# W104X.net
KiCad netlist of a schematic drawn in EAGLE
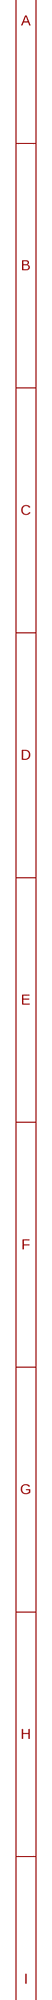
[diagram p0: schematic, sheet 1, part 1 of 2]
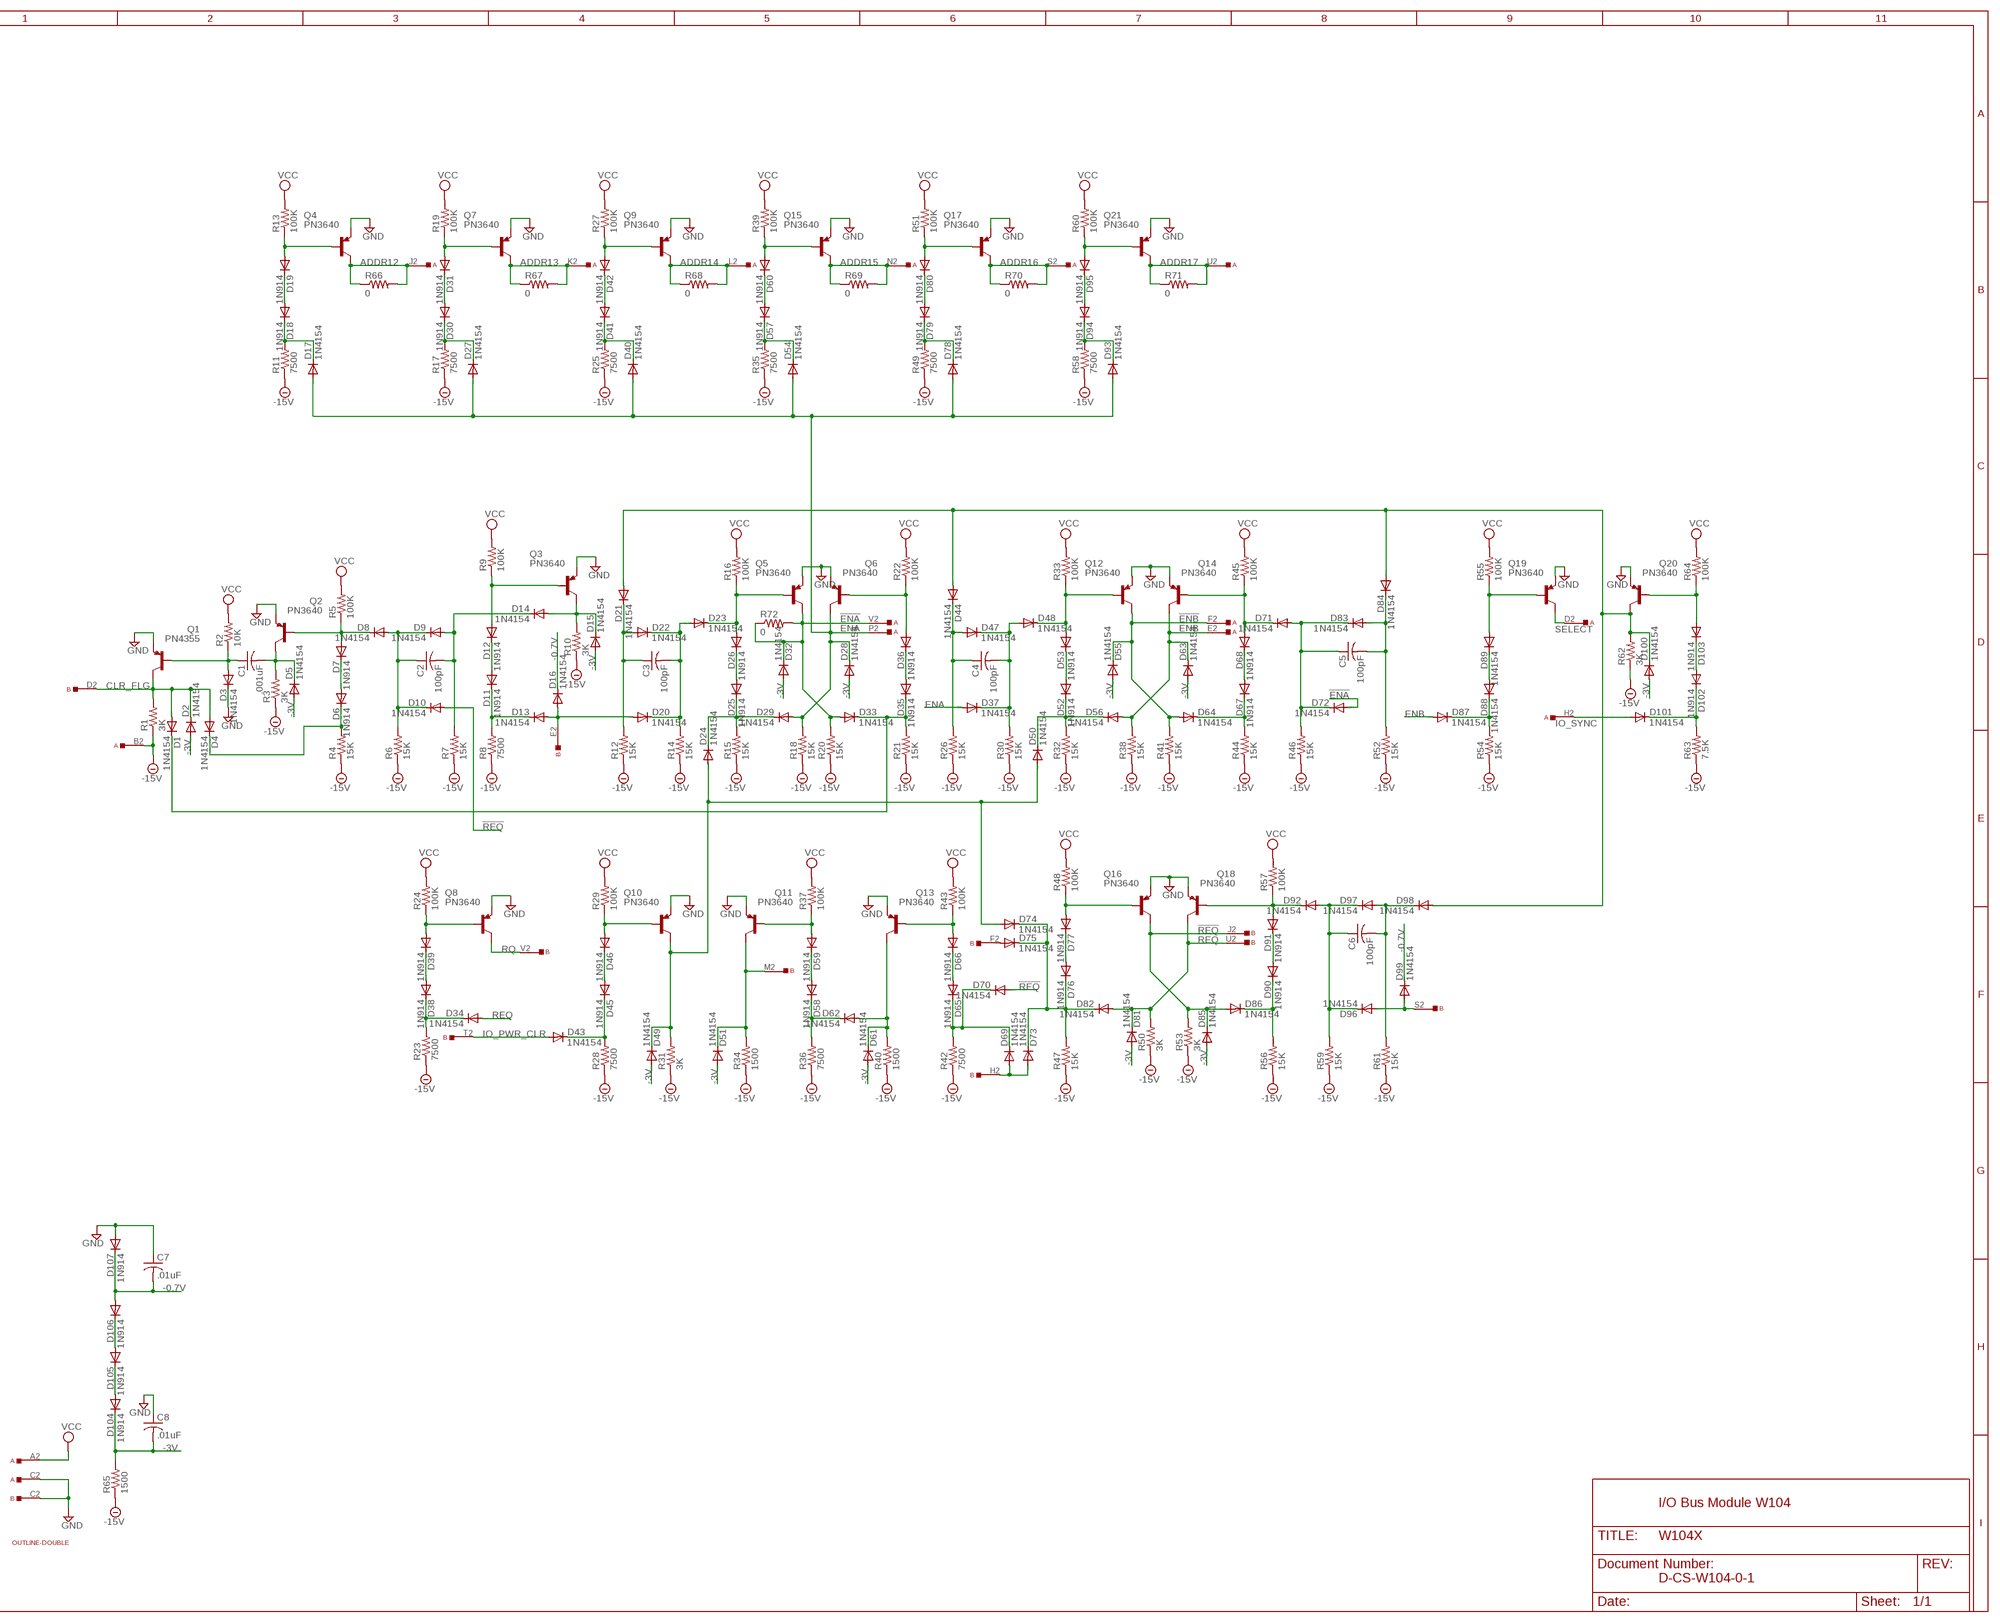
[diagram p1: schematic, sheet 1, part 2 of 2]

(export (version "E")
  (design (tool "Eeschema 10.0.6"))
  (components
    (comp (ref "A")
      (value "SS-TOP")
      (footprint "eagle-import:EDGE-CON1")
      (libsource (lib "eagle-import") (part "SS-TOP"))
    )
    (comp (ref "B")
      (value "SS-TOP")
      (footprint "eagle-import:EDGE-CON1")
      (libsource (lib "eagle-import") (part "SS-TOP"))
    )
    (comp (ref "C1")
      (value ".001uF")
      (footprint "eagle-import:C063-025X075")
      (libsource (lib "eagle-import") (part "C-US"))
    )
    (comp (ref "C2")
      (value "100pF")
      (footprint "eagle-import:C150-054X183")
      (libsource (lib "eagle-import") (part "C-US150-054X183"))
    )
    (comp (ref "C3")
      (value "100pF")
      (footprint "eagle-import:C150-054X183")
      (libsource (lib "eagle-import") (part "C-US150-054X183"))
    )
    (comp (ref "C4")
      (value "100pF")
      (footprint "eagle-import:C150-054X183")
      (libsource (lib "eagle-import") (part "C-US150-054X183"))
    )
    (comp (ref "C5")
      (value "100pF")
      (footprint "eagle-import:C150-054X183")
      (libsource (lib "eagle-import") (part "C-US150-054X183"))
    )
    (comp (ref "C6")
      (value "100pF")
      (footprint "eagle-import:C150-054X183")
      (libsource (lib "eagle-import") (part "C-US150-054X183"))
    )
    (comp (ref "C7")
      (value ".01uF")
      (footprint "eagle-import:C063-025X075")
      (libsource (lib "eagle-import") (part "C-US"))
    )
    (comp (ref "C8")
      (value ".01uF")
      (footprint "eagle-import:C063-025X075")
      (libsource (lib "eagle-import") (part "C-US"))
    )
    (comp (ref "D1")
      (value "1N4154")
      (footprint "eagle-import:DO35-10")
      (libsource (lib "eagle-import") (part "DIODE-DO35-10"))
    )
    (comp (ref "D2")
      (value "1N4154")
      (footprint "eagle-import:DO35-10")
      (libsource (lib "eagle-import") (part "DIODE-DO35-10"))
    )
    (comp (ref "D3")
      (value "1N4154")
      (footprint "eagle-import:DO35-10")
      (libsource (lib "eagle-import") (part "DIODE-DO35-10"))
    )
    (comp (ref "D4")
      (value "1N4154")
      (footprint "eagle-import:DO35-10")
      (libsource (lib "eagle-import") (part "DIODE-DO35-10"))
    )
    (comp (ref "D5")
      (value "1N4154")
      (footprint "eagle-import:DO35-10")
      (libsource (lib "eagle-import") (part "DIODE-DO35-10"))
    )
    (comp (ref "D6")
      (value "1N914")
      (footprint "eagle-import:DO35-10")
      (libsource (lib "eagle-import") (part "DIODE-DO35-10"))
    )
    (comp (ref "D7")
      (value "1N914")
      (footprint "eagle-import:DO35-10")
      (libsource (lib "eagle-import") (part "DIODE-DO35-10"))
    )
    (comp (ref "D8")
      (value "1N4154")
      (footprint "eagle-import:DO35-10")
      (libsource (lib "eagle-import") (part "DIODE-DO35-10"))
    )
    (comp (ref "D9")
      (value "1N4154")
      (footprint "eagle-import:DO35-10")
      (libsource (lib "eagle-import") (part "DIODE-DO35-10"))
    )
    (comp (ref "D10")
      (value "1N4154")
      (footprint "eagle-import:DO35-10")
      (libsource (lib "eagle-import") (part "DIODE-DO35-10"))
    )
    (comp (ref "D11")
      (value "1N914")
      (footprint "eagle-import:DO35-10")
      (libsource (lib "eagle-import") (part "DIODE-DO35-10"))
    )
    (comp (ref "D12")
      (value "1N914")
      (footprint "eagle-import:DO35-10")
      (libsource (lib "eagle-import") (part "DIODE-DO35-10"))
    )
    (comp (ref "D13")
      (value "1N4154")
      (footprint "eagle-import:DO35-10")
      (libsource (lib "eagle-import") (part "DIODE-DO35-10"))
    )
    (comp (ref "D14")
      (value "1N4154")
      (footprint "eagle-import:DO35-10")
      (libsource (lib "eagle-import") (part "DIODE-DO35-10"))
    )
    (comp (ref "D15")
      (value "1N4154")
      (footprint "eagle-import:DO35-10")
      (libsource (lib "eagle-import") (part "DIODE-DO35-10"))
    )
    (comp (ref "D16")
      (value "1N4154")
      (footprint "eagle-import:DO35-10")
      (libsource (lib "eagle-import") (part "DIODE-DO35-10"))
    )
    (comp (ref "D17")
      (value "1N4154")
      (footprint "eagle-import:DO35-10")
      (libsource (lib "eagle-import") (part "DIODE-DO35-10"))
    )
    (comp (ref "D18")
      (value "1N914")
      (footprint "eagle-import:DO35-10")
      (libsource (lib "eagle-import") (part "DIODE-DO35-10"))
    )
    (comp (ref "D19")
      (value "1N914")
      (footprint "eagle-import:DO35-10")
      (libsource (lib "eagle-import") (part "DIODE-DO35-10"))
    )
    (comp (ref "D20")
      (value "1N4154")
      (footprint "eagle-import:DO35-10")
      (libsource (lib "eagle-import") (part "DIODE-DO35-10"))
    )
    (comp (ref "D21")
      (value "1N4154")
      (footprint "eagle-import:DO35-10")
      (libsource (lib "eagle-import") (part "DIODE-DO35-10"))
    )
    (comp (ref "D22")
      (value "1N4154")
      (footprint "eagle-import:DO35-10")
      (libsource (lib "eagle-import") (part "DIODE-DO35-10"))
    )
    (comp (ref "D23")
      (value "1N4154")
      (footprint "eagle-import:DO35-10")
      (libsource (lib "eagle-import") (part "DIODE-DO35-10"))
    )
    (comp (ref "D24")
      (value "1N4154")
      (footprint "eagle-import:DO35-10")
      (libsource (lib "eagle-import") (part "DIODE-DO35-10"))
    )
    (comp (ref "D25")
      (value "1N914")
      (footprint "eagle-import:DO35-10")
      (libsource (lib "eagle-import") (part "DIODE-DO35-10"))
    )
    (comp (ref "D26")
      (value "1N914")
      (footprint "eagle-import:DO35-10")
      (libsource (lib "eagle-import") (part "DIODE-DO35-10"))
    )
    (comp (ref "D27")
      (value "1N4154")
      (footprint "eagle-import:DO35-10")
      (libsource (lib "eagle-import") (part "DIODE-DO35-10"))
    )
    (comp (ref "D28")
      (value "1N4154")
      (footprint "eagle-import:DO35-10")
      (libsource (lib "eagle-import") (part "DIODE-DO35-10"))
    )
    (comp (ref "D29")
      (value "1N4154")
      (footprint "eagle-import:DO35-10")
      (libsource (lib "eagle-import") (part "DIODE-DO35-10"))
    )
    (comp (ref "D30")
      (value "1N914")
      (footprint "eagle-import:DO35-10")
      (libsource (lib "eagle-import") (part "DIODE-DO35-10"))
    )
    (comp (ref "D31")
      (value "1N914")
      (footprint "eagle-import:DO35-10")
      (libsource (lib "eagle-import") (part "DIODE-DO35-10"))
    )
    (comp (ref "D32")
      (value "1N4154")
      (footprint "eagle-import:DO35-10")
      (libsource (lib "eagle-import") (part "DIODE-DO35-10"))
    )
    (comp (ref "D33")
      (value "1N4154")
      (footprint "eagle-import:DO35-10")
      (libsource (lib "eagle-import") (part "DIODE-DO35-10"))
    )
    (comp (ref "D34")
      (value "1N4154")
      (footprint "eagle-import:DO35-10")
      (libsource (lib "eagle-import") (part "DIODE-DO35-10"))
    )
    (comp (ref "D35")
      (value "1N914")
      (footprint "eagle-import:DO35-10")
      (libsource (lib "eagle-import") (part "DIODE-DO35-10"))
    )
    (comp (ref "D36")
      (value "1N914")
      (footprint "eagle-import:DO35-10")
      (libsource (lib "eagle-import") (part "DIODE-DO35-10"))
    )
    (comp (ref "D37")
      (value "1N4154")
      (footprint "eagle-import:DO35-10")
      (libsource (lib "eagle-import") (part "DIODE-DO35-10"))
    )
    (comp (ref "D38")
      (value "1N914")
      (footprint "eagle-import:DO35-10")
      (libsource (lib "eagle-import") (part "DIODE-DO35-10"))
    )
    (comp (ref "D39")
      (value "1N914")
      (footprint "eagle-import:DO35-10")
      (libsource (lib "eagle-import") (part "DIODE-DO35-10"))
    )
    (comp (ref "D40")
      (value "1N4154")
      (footprint "eagle-import:DO35-10")
      (libsource (lib "eagle-import") (part "DIODE-DO35-10"))
    )
    (comp (ref "D41")
      (value "1N914")
      (footprint "eagle-import:DO35-10")
      (libsource (lib "eagle-import") (part "DIODE-DO35-10"))
    )
    (comp (ref "D42")
      (value "1N914")
      (footprint "eagle-import:DO35-10")
      (libsource (lib "eagle-import") (part "DIODE-DO35-10"))
    )
    (comp (ref "D43")
      (value "1N4154")
      (footprint "eagle-import:DO35-10")
      (libsource (lib "eagle-import") (part "DIODE-DO35-10"))
    )
    (comp (ref "D44")
      (value "1N4154")
      (footprint "eagle-import:DO35-10")
      (libsource (lib "eagle-import") (part "DIODE-DO35-10"))
    )
    (comp (ref "D45")
      (value "1N914")
      (footprint "eagle-import:DO35-10")
      (libsource (lib "eagle-import") (part "DIODE-DO35-10"))
    )
    (comp (ref "D46")
      (value "1N914")
      (footprint "eagle-import:DO35-10")
      (libsource (lib "eagle-import") (part "DIODE-DO35-10"))
    )
    (comp (ref "D47")
      (value "1N4154")
      (footprint "eagle-import:DO35-10")
      (libsource (lib "eagle-import") (part "DIODE-DO35-10"))
    )
    (comp (ref "D48")
      (value "1N4154")
      (footprint "eagle-import:DO35-10")
      (libsource (lib "eagle-import") (part "DIODE-DO35-10"))
    )
    (comp (ref "D49")
      (value "1N4154")
      (footprint "eagle-import:DO35-10")
      (libsource (lib "eagle-import") (part "DIODE-DO35-10"))
    )
    (comp (ref "D50")
      (value "1N4154")
      (footprint "eagle-import:DO35-10")
      (libsource (lib "eagle-import") (part "DIODE-DO35-10"))
    )
    (comp (ref "D51")
      (value "1N4154")
      (footprint "eagle-import:DO35-10")
      (libsource (lib "eagle-import") (part "DIODE-DO35-10"))
    )
    (comp (ref "D52")
      (value "1N914")
      (footprint "eagle-import:DO35-10")
      (libsource (lib "eagle-import") (part "DIODE-DO35-10"))
    )
    (comp (ref "D53")
      (value "1N914")
      (footprint "eagle-import:DO35-10")
      (libsource (lib "eagle-import") (part "DIODE-DO35-10"))
    )
    (comp (ref "D54")
      (value "1N4154")
      (footprint "eagle-import:DO35-10")
      (libsource (lib "eagle-import") (part "DIODE-DO35-10"))
    )
    (comp (ref "D55")
      (value "1N4154")
      (footprint "eagle-import:DO35-10")
      (libsource (lib "eagle-import") (part "DIODE-DO35-10"))
    )
    (comp (ref "D56")
      (value "1N4154")
      (footprint "eagle-import:DO35-10")
      (libsource (lib "eagle-import") (part "DIODE-DO35-10"))
    )
    (comp (ref "D57")
      (value "1N914")
      (footprint "eagle-import:DO35-10")
      (libsource (lib "eagle-import") (part "DIODE-DO35-10"))
    )
    (comp (ref "D58")
      (value "1N914")
      (footprint "eagle-import:DO35-10")
      (libsource (lib "eagle-import") (part "DIODE-DO35-10"))
    )
    (comp (ref "D59")
      (value "1N914")
      (footprint "eagle-import:DO35-10")
      (libsource (lib "eagle-import") (part "DIODE-DO35-10"))
    )
    (comp (ref "D60")
      (value "1N914")
      (footprint "eagle-import:DO35-10")
      (libsource (lib "eagle-import") (part "DIODE-DO35-10"))
    )
    (comp (ref "D61")
      (value "1N4154")
      (footprint "eagle-import:DO35-10")
      (libsource (lib "eagle-import") (part "DIODE-DO35-10"))
    )
    (comp (ref "D62")
      (value "1N4154")
      (footprint "eagle-import:DO35-10")
      (libsource (lib "eagle-import") (part "DIODE-DO35-10"))
    )
    (comp (ref "D63")
      (value "1N4154")
      (footprint "eagle-import:DO35-10")
      (libsource (lib "eagle-import") (part "DIODE-DO35-10"))
    )
    (comp (ref "D64")
      (value "1N4154")
      (footprint "eagle-import:DO35-10")
      (libsource (lib "eagle-import") (part "DIODE-DO35-10"))
    )
    (comp (ref "D65")
      (value "1N914")
      (footprint "eagle-import:DO35-10")
      (libsource (lib "eagle-import") (part "DIODE-DO35-10"))
    )
    (comp (ref "D66")
      (value "1N914")
      (footprint "eagle-import:DO35-10")
      (libsource (lib "eagle-import") (part "DIODE-DO35-10"))
    )
    (comp (ref "D67")
      (value "1N914")
      (footprint "eagle-import:DO35-10")
      (libsource (lib "eagle-import") (part "DIODE-DO35-10"))
    )
    (comp (ref "D68")
      (value "1N914")
      (footprint "eagle-import:DO35-10")
      (libsource (lib "eagle-import") (part "DIODE-DO35-10"))
    )
    (comp (ref "D69")
      (value "1N4154")
      (footprint "eagle-import:DO35-10")
      (libsource (lib "eagle-import") (part "DIODE-DO35-10"))
    )
    (comp (ref "D70")
      (value "1N4154")
      (footprint "eagle-import:DO35-10")
      (libsource (lib "eagle-import") (part "DIODE-DO35-10"))
    )
    (comp (ref "D71")
      (value "1N4154")
      (footprint "eagle-import:DO35-10")
      (libsource (lib "eagle-import") (part "DIODE-DO35-10"))
    )
    (comp (ref "D72")
      (value "1N4154")
      (footprint "eagle-import:DO35-10")
      (libsource (lib "eagle-import") (part "DIODE-DO35-10"))
    )
    (comp (ref "D73")
      (value "1N4154")
      (footprint "eagle-import:DO35-10")
      (libsource (lib "eagle-import") (part "DIODE-DO35-10"))
    )
    (comp (ref "D74")
      (value "1N4154")
      (footprint "eagle-import:DO35-10")
      (libsource (lib "eagle-import") (part "DIODE-DO35-10"))
    )
    (comp (ref "D75")
      (value "1N4154")
      (footprint "eagle-import:DO35-10")
      (libsource (lib "eagle-import") (part "DIODE-DO35-10"))
    )
    (comp (ref "D76")
      (value "1N914")
      (footprint "eagle-import:DO35-10")
      (libsource (lib "eagle-import") (part "DIODE-DO35-10"))
    )
    (comp (ref "D77")
      (value "1N914")
      (footprint "eagle-import:DO35-10")
      (libsource (lib "eagle-import") (part "DIODE-DO35-10"))
    )
    (comp (ref "D78")
      (value "1N4154")
      (footprint "eagle-import:DO35-10")
      (libsource (lib "eagle-import") (part "DIODE-DO35-10"))
    )
    (comp (ref "D79")
      (value "1N914")
      (footprint "eagle-import:DO35-10")
      (libsource (lib "eagle-import") (part "DIODE-DO35-10"))
    )
    (comp (ref "D80")
      (value "1N914")
      (footprint "eagle-import:DO35-10")
      (libsource (lib "eagle-import") (part "DIODE-DO35-10"))
    )
    (comp (ref "D81")
      (value "1N4154")
      (footprint "eagle-import:DO35-10")
      (libsource (lib "eagle-import") (part "DIODE-DO35-10"))
    )
    (comp (ref "D82")
      (value "1N4154")
      (footprint "eagle-import:DO35-10")
      (libsource (lib "eagle-import") (part "DIODE-DO35-10"))
    )
    (comp (ref "D83")
      (value "1N4154")
      (footprint "eagle-import:DO35-10")
      (libsource (lib "eagle-import") (part "DIODE-DO35-10"))
    )
    (comp (ref "D84")
      (value "1N4154")
      (footprint "eagle-import:DO35-10")
      (libsource (lib "eagle-import") (part "DIODE-DO35-10"))
    )
    (comp (ref "D85")
      (value "1N4154")
      (footprint "eagle-import:DO35-10")
      (libsource (lib "eagle-import") (part "DIODE-DO35-10"))
    )
    (comp (ref "D86")
      (value "1N4154")
      (footprint "eagle-import:DO35-10")
      (libsource (lib "eagle-import") (part "DIODE-DO35-10"))
    )
    (comp (ref "D87")
      (value "1N4154")
      (footprint "eagle-import:DO35-10")
      (libsource (lib "eagle-import") (part "DIODE-DO35-10"))
    )
    (comp (ref "D88")
      (value "1N4154")
      (footprint "eagle-import:DO35-10")
      (libsource (lib "eagle-import") (part "DIODE-DO35-10"))
    )
    (comp (ref "D89")
      (value "1N4154")
      (footprint "eagle-import:DO35-10")
      (libsource (lib "eagle-import") (part "DIODE-DO35-10"))
    )
    (comp (ref "D90")
      (value "1N914")
      (footprint "eagle-import:DO35-10")
      (libsource (lib "eagle-import") (part "DIODE-DO35-10"))
    )
    (comp (ref "D91")
      (value "1N914")
      (footprint "eagle-import:DO35-10")
      (libsource (lib "eagle-import") (part "DIODE-DO35-10"))
    )
    (comp (ref "D92")
      (value "1N4154")
      (footprint "eagle-import:DO35-10")
      (libsource (lib "eagle-import") (part "DIODE-DO35-10"))
    )
    (comp (ref "D93")
      (value "1N4154")
      (footprint "eagle-import:DO35-10")
      (libsource (lib "eagle-import") (part "DIODE-DO35-10"))
    )
    (comp (ref "D94")
      (value "1N914")
      (footprint "eagle-import:DO35-10")
      (libsource (lib "eagle-import") (part "DIODE-DO35-10"))
    )
    (comp (ref "D95")
      (value "1N914")
      (footprint "eagle-import:DO35-10")
      (libsource (lib "eagle-import") (part "DIODE-DO35-10"))
    )
    (comp (ref "D96")
      (value "1N4154")
      (footprint "eagle-import:DO35-10")
      (libsource (lib "eagle-import") (part "DIODE-DO35-10"))
    )
    (comp (ref "D97")
      (value "1N4154")
      (footprint "eagle-import:DO35-10")
      (libsource (lib "eagle-import") (part "DIODE-DO35-10"))
    )
    (comp (ref "D98")
      (value "1N4154")
      (footprint "eagle-import:DO35-10")
      (libsource (lib "eagle-import") (part "DIODE-DO35-10"))
    )
    (comp (ref "D99")
      (value "1N4154")
      (footprint "eagle-import:DO35-10")
      (libsource (lib "eagle-import") (part "DIODE-DO35-10"))
    )
    (comp (ref "D100")
      (value "1N4154")
      (footprint "eagle-import:DO35-10")
      (libsource (lib "eagle-import") (part "DIODE-DO35-10"))
    )
    (comp (ref "D101")
      (value "1N4154")
      (footprint "eagle-import:DO35-10")
      (libsource (lib "eagle-import") (part "DIODE-DO35-10"))
    )
    (comp (ref "D102")
      (value "1N914")
      (footprint "eagle-import:DO35-10")
      (libsource (lib "eagle-import") (part "DIODE-DO35-10"))
    )
    (comp (ref "D103")
      (value "1N914")
      (footprint "eagle-import:DO35-10")
      (libsource (lib "eagle-import") (part "DIODE-DO35-10"))
    )
    (comp (ref "D104")
      (value "1N914")
      (footprint "eagle-import:DO35-10")
      (libsource (lib "eagle-import") (part "DIODE-DO35-10"))
    )
    (comp (ref "D105")
      (value "1N914")
      (footprint "eagle-import:DO35-10")
      (libsource (lib "eagle-import") (part "DIODE-DO35-10"))
    )
    (comp (ref "D106")
      (value "1N914")
      (footprint "eagle-import:DO35-10")
      (libsource (lib "eagle-import") (part "DIODE-DO35-10"))
    )
    (comp (ref "D107")
      (value "1N914")
      (footprint "eagle-import:DO35-10")
      (libsource (lib "eagle-import") (part "DIODE-DO35-10"))
    )
    (comp (ref "Q1")
      (value "PN4355")
      (footprint "eagle-import:TO5")
      (libsource (lib "eagle-import") (part "-PNP-TO5"))
    )
    (comp (ref "Q2")
      (value "PN3640")
      (footprint "eagle-import:TO5")
      (libsource (lib "eagle-import") (part "-PNP-TO5"))
    )
    (comp (ref "Q3")
      (value "PN3640")
      (footprint "eagle-import:TO5")
      (libsource (lib "eagle-import") (part "-PNP-TO5"))
    )
    (comp (ref "Q4")
      (value "PN3640")
      (footprint "eagle-import:TO5")
      (libsource (lib "eagle-import") (part "-PNP-TO5"))
    )
    (comp (ref "Q5")
      (value "PN3640")
      (footprint "eagle-import:TO5")
      (libsource (lib "eagle-import") (part "-PNP-TO5"))
    )
    (comp (ref "Q6")
      (value "PN3640")
      (footprint "eagle-import:TO5")
      (libsource (lib "eagle-import") (part "-PNP-TO5"))
    )
    (comp (ref "Q7")
      (value "PN3640")
      (footprint "eagle-import:TO5")
      (libsource (lib "eagle-import") (part "-PNP-TO5"))
    )
    (comp (ref "Q8")
      (value "PN3640")
      (footprint "eagle-import:TO5")
      (libsource (lib "eagle-import") (part "-PNP-TO5"))
    )
    (comp (ref "Q9")
      (value "PN3640")
      (footprint "eagle-import:TO5")
      (libsource (lib "eagle-import") (part "-PNP-TO5"))
    )
    (comp (ref "Q10")
      (value "PN3640")
      (footprint "eagle-import:TO5")
      (libsource (lib "eagle-import") (part "-PNP-TO5"))
    )
    (comp (ref "Q11")
      (value "PN3640")
      (footprint "eagle-import:TO5")
      (libsource (lib "eagle-import") (part "-PNP-TO5"))
    )
    (comp (ref "Q12")
      (value "PN3640")
      (footprint "eagle-import:TO5")
      (libsource (lib "eagle-import") (part "-PNP-TO5"))
    )
    (comp (ref "Q13")
      (value "PN3640")
      (footprint "eagle-import:TO5")
      (libsource (lib "eagle-import") (part "-PNP-TO5"))
    )
    (comp (ref "Q14")
      (value "PN3640")
      (footprint "eagle-import:TO5")
      (libsource (lib "eagle-import") (part "-PNP-TO5"))
    )
    (comp (ref "Q15")
      (value "PN3640")
      (footprint "eagle-import:TO5")
      (libsource (lib "eagle-import") (part "-PNP-TO5"))
    )
    (comp (ref "Q16")
      (value "PN3640")
      (footprint "eagle-import:TO5")
      (libsource (lib "eagle-import") (part "-PNP-TO5"))
    )
    (comp (ref "Q17")
      (value "PN3640")
      (footprint "eagle-import:TO5")
      (libsource (lib "eagle-import") (part "-PNP-TO5"))
    )
    (comp (ref "Q18")
      (value "PN3640")
      (footprint "eagle-import:TO5")
      (libsource (lib "eagle-import") (part "-PNP-TO5"))
    )
    (comp (ref "Q19")
      (value "PN3640")
      (footprint "eagle-import:TO5")
      (libsource (lib "eagle-import") (part "-PNP-TO5"))
    )
    (comp (ref "Q20")
      (value "PN3640")
      (footprint "eagle-import:TO5")
      (libsource (lib "eagle-import") (part "-PNP-TO5"))
    )
    (comp (ref "Q21")
      (value "PN3640")
      (footprint "eagle-import:TO5")
      (libsource (lib "eagle-import") (part "-PNP-TO5"))
    )
    (comp (ref "R1")
      (value "3K")
      (footprint "eagle-import:0207_10")
      (libsource (lib "eagle-import") (part "R-US_0207/10"))
    )
    (comp (ref "R2")
      (value "10K")
      (footprint "eagle-import:0207_10")
      (libsource (lib "eagle-import") (part "R-US_0207/10"))
    )
    (comp (ref "R3")
      (value "3K")
      (footprint "eagle-import:0207_10")
      (libsource (lib "eagle-import") (part "R-US_0207/10"))
    )
    (comp (ref "R4")
      (value "15K")
      (footprint "eagle-import:0207_10")
      (libsource (lib "eagle-import") (part "R-US_0207/10"))
    )
    (comp (ref "R5")
      (value "100K")
      (footprint "eagle-import:0207_10")
      (libsource (lib "eagle-import") (part "R-US_0207/10"))
    )
    (comp (ref "R6")
      (value "15K")
      (footprint "eagle-import:0207_10")
      (libsource (lib "eagle-import") (part "R-US_0207/10"))
    )
    (comp (ref "R7")
      (value "15K")
      (footprint "eagle-import:0207_10")
      (libsource (lib "eagle-import") (part "R-US_0207/10"))
    )
    (comp (ref "R8")
      (value "7500")
      (footprint "eagle-import:0207_10")
      (libsource (lib "eagle-import") (part "R-US_0207/10"))
    )
    (comp (ref "R9")
      (value "100K")
      (footprint "eagle-import:0207_10")
      (libsource (lib "eagle-import") (part "R-US_0207/10"))
    )
    (comp (ref "R10")
      (value "3K")
      (footprint "eagle-import:0207_10")
      (libsource (lib "eagle-import") (part "R-US_0207/10"))
    )
    (comp (ref "R11")
      (value "7500")
      (footprint "eagle-import:0207_10")
      (libsource (lib "eagle-import") (part "R-US_0207/10"))
    )
    (comp (ref "R12")
      (value "15K")
      (footprint "eagle-import:0207_10")
      (libsource (lib "eagle-import") (part "R-US_0207/10"))
    )
    (comp (ref "R13")
      (value "100K")
      (footprint "eagle-import:0207_10")
      (libsource (lib "eagle-import") (part "R-US_0207/10"))
    )
    (comp (ref "R14")
      (value "15K")
      (footprint "eagle-import:0207_10")
      (libsource (lib "eagle-import") (part "R-US_0207/10"))
    )
    (comp (ref "R15")
      (value "15K")
      (footprint "eagle-import:0207_10")
      (libsource (lib "eagle-import") (part "R-US_0207/10"))
    )
    (comp (ref "R16")
      (value "100K")
      (footprint "eagle-import:0207_10")
      (libsource (lib "eagle-import") (part "R-US_0207/10"))
    )
    (comp (ref "R17")
      (value "7500")
      (footprint "eagle-import:0207_10")
      (libsource (lib "eagle-import") (part "R-US_0207/10"))
    )
    (comp (ref "R18")
      (value "15K")
      (footprint "eagle-import:0207_10")
      (libsource (lib "eagle-import") (part "R-US_0207/10"))
    )
    (comp (ref "R19")
      (value "100K")
      (footprint "eagle-import:0207_10")
      (libsource (lib "eagle-import") (part "R-US_0207/10"))
    )
    (comp (ref "R20")
      (value "15K")
      (footprint "eagle-import:0207_10")
      (libsource (lib "eagle-import") (part "R-US_0207/10"))
    )
    (comp (ref "R21")
      (value "15K")
      (footprint "eagle-import:0207_10")
      (libsource (lib "eagle-import") (part "R-US_0207/10"))
    )
    (comp (ref "R22")
      (value "100K")
      (footprint "eagle-import:0207_10")
      (libsource (lib "eagle-import") (part "R-US_0207/10"))
    )
    (comp (ref "R23")
      (value "7500")
      (footprint "eagle-import:0207_10")
      (libsource (lib "eagle-import") (part "R-US_0207/10"))
    )
    (comp (ref "R24")
      (value "100K")
      (footprint "eagle-import:0207_10")
      (libsource (lib "eagle-import") (part "R-US_0207/10"))
    )
    (comp (ref "R25")
      (value "7500")
      (footprint "eagle-import:0207_10")
      (libsource (lib "eagle-import") (part "R-US_0207/10"))
    )
    (comp (ref "R26")
      (value "15K")
      (footprint "eagle-import:0207_10")
      (libsource (lib "eagle-import") (part "R-US_0207/10"))
    )
    (comp (ref "R27")
      (value "100K")
      (footprint "eagle-import:0207_10")
      (libsource (lib "eagle-import") (part "R-US_0207/10"))
    )
    (comp (ref "R28")
      (value "7500")
      (footprint "eagle-import:0207_10")
      (libsource (lib "eagle-import") (part "R-US_0207/10"))
    )
    (comp (ref "R29")
      (value "100K")
      (footprint "eagle-import:0207_10")
      (libsource (lib "eagle-import") (part "R-US_0207/10"))
    )
    (comp (ref "R30")
      (value "15K")
      (footprint "eagle-import:0207_10")
      (libsource (lib "eagle-import") (part "R-US_0207/10"))
    )
    (comp (ref "R31")
      (value "3K")
      (footprint "eagle-import:0207_10")
      (libsource (lib "eagle-import") (part "R-US_0207/10"))
    )
    (comp (ref "R32")
      (value "15K")
      (footprint "eagle-import:0207_10")
      (libsource (lib "eagle-import") (part "R-US_0207/10"))
    )
    (comp (ref "R33")
      (value "100K")
      (footprint "eagle-import:0207_10")
      (libsource (lib "eagle-import") (part "R-US_0207/10"))
    )
    (comp (ref "R34")
      (value "1500")
      (footprint "eagle-import:0207_10")
      (libsource (lib "eagle-import") (part "R-US_0207/10"))
    )
    (comp (ref "R35")
      (value "7500")
      (footprint "eagle-import:0207_10")
      (libsource (lib "eagle-import") (part "R-US_0207/10"))
    )
    (comp (ref "R36")
      (value "7500")
      (footprint "eagle-import:0207_10")
      (libsource (lib "eagle-import") (part "R-US_0207/10"))
    )
    (comp (ref "R37")
      (value "100K")
      (footprint "eagle-import:0207_10")
      (libsource (lib "eagle-import") (part "R-US_0207/10"))
    )
    (comp (ref "R38")
      (value "15K")
      (footprint "eagle-import:0207_10")
      (libsource (lib "eagle-import") (part "R-US_0207/10"))
    )
    (comp (ref "R39")
      (value "100K")
      (footprint "eagle-import:0207_10")
      (libsource (lib "eagle-import") (part "R-US_0207/10"))
    )
    (comp (ref "R40")
      (value "1500")
      (footprint "eagle-import:0207_10")
      (libsource (lib "eagle-import") (part "R-US_0207/10"))
    )
    (comp (ref "R41")
      (value "15K")
      (footprint "eagle-import:0207_10")
      (libsource (lib "eagle-import") (part "R-US_0207/10"))
    )
    (comp (ref "R42")
      (value "7500")
      (footprint "eagle-import:0207_10")
      (libsource (lib "eagle-import") (part "R-US_0207/10"))
    )
    (comp (ref "R43")
      (value "100K")
      (footprint "eagle-import:0207_10")
      (libsource (lib "eagle-import") (part "R-US_0207/10"))
    )
    (comp (ref "R44")
      (value "15K")
      (footprint "eagle-import:0207_10")
      (libsource (lib "eagle-import") (part "R-US_0207/10"))
    )
    (comp (ref "R45")
      (value "100K")
      (footprint "eagle-import:0207_10")
      (libsource (lib "eagle-import") (part "R-US_0207/10"))
    )
    (comp (ref "R46")
      (value "15K")
      (footprint "eagle-import:0207_10")
      (libsource (lib "eagle-import") (part "R-US_0207/10"))
    )
    (comp (ref "R47")
      (value "15K")
      (footprint "eagle-import:0207_10")
      (libsource (lib "eagle-import") (part "R-US_0207/10"))
    )
    (comp (ref "R48")
      (value "100K")
      (footprint "eagle-import:0207_10")
      (libsource (lib "eagle-import") (part "R-US_0207/10"))
    )
    (comp (ref "R49")
      (value "7500")
      (footprint "eagle-import:0207_10")
      (libsource (lib "eagle-import") (part "R-US_0207/10"))
    )
    (comp (ref "R50")
      (value "3K")
      (footprint "eagle-import:0207_10")
      (libsource (lib "eagle-import") (part "R-US_0207/10"))
    )
    (comp (ref "R51")
      (value "100K")
      (footprint "eagle-import:0207_10")
      (libsource (lib "eagle-import") (part "R-US_0207/10"))
    )
    (comp (ref "R52")
      (value "15K")
      (footprint "eagle-import:0207_10")
      (libsource (lib "eagle-import") (part "R-US_0207/10"))
    )
    (comp (ref "R53")
      (value "3K")
      (footprint "eagle-import:0207_10")
      (libsource (lib "eagle-import") (part "R-US_0207/10"))
    )
    (comp (ref "R54")
      (value "15K")
      (footprint "eagle-import:0207_10")
      (libsource (lib "eagle-import") (part "R-US_0207/10"))
    )
    (comp (ref "R55")
      (value "100K")
      (footprint "eagle-import:0207_10")
      (libsource (lib "eagle-import") (part "R-US_0207/10"))
    )
    (comp (ref "R56")
      (value "15K")
      (footprint "eagle-import:0207_10")
      (libsource (lib "eagle-import") (part "R-US_0207/10"))
    )
    (comp (ref "R57")
      (value "100K")
      (footprint "eagle-import:0207_10")
      (libsource (lib "eagle-import") (part "R-US_0207/10"))
    )
    (comp (ref "R58")
      (value "7500")
      (footprint "eagle-import:0207_10")
      (libsource (lib "eagle-import") (part "R-US_0207/10"))
    )
    (comp (ref "R59")
      (value "15K")
      (footprint "eagle-import:0207_10")
      (libsource (lib "eagle-import") (part "R-US_0207/10"))
    )
    (comp (ref "R60")
      (value "100K")
      (footprint "eagle-import:0207_10")
      (libsource (lib "eagle-import") (part "R-US_0207/10"))
    )
    (comp (ref "R61")
      (value "15K")
      (footprint "eagle-import:0207_10")
      (libsource (lib "eagle-import") (part "R-US_0207/10"))
    )
    (comp (ref "R62")
      (value "3K")
      (footprint "eagle-import:0207_10")
      (libsource (lib "eagle-import") (part "R-US_0207/10"))
    )
    (comp (ref "R63")
      (value "7.5K")
      (footprint "eagle-import:0207_10")
      (libsource (lib "eagle-import") (part "R-US_0207/10"))
    )
    (comp (ref "R64")
      (value "100K")
      (footprint "eagle-import:0207_10")
      (libsource (lib "eagle-import") (part "R-US_0207/10"))
    )
    (comp (ref "R65")
      (value "1500")
      (footprint "eagle-import:0207_10")
      (libsource (lib "eagle-import") (part "R-US_0207/10"))
    )
    (comp (ref "R66")
      (value "0")
      (footprint "eagle-import:0207_10")
      (libsource (lib "eagle-import") (part "R-US_0207/10"))
    )
    (comp (ref "R67")
      (value "0")
      (footprint "eagle-import:0207_10")
      (libsource (lib "eagle-import") (part "R-US_0207/10"))
    )
    (comp (ref "R68")
      (value "0")
      (footprint "eagle-import:0207_10")
      (libsource (lib "eagle-import") (part "R-US_0207/10"))
    )
    (comp (ref "R69")
      (value "0")
      (footprint "eagle-import:0207_10")
      (libsource (lib "eagle-import") (part "R-US_0207/10"))
    )
    (comp (ref "R70")
      (value "0")
      (footprint "eagle-import:0207_10")
      (libsource (lib "eagle-import") (part "R-US_0207/10"))
    )
    (comp (ref "R71")
      (value "0")
      (footprint "eagle-import:0207_10")
      (libsource (lib "eagle-import") (part "R-US_0207/10"))
    )
    (comp (ref "R72")
      (value "0")
      (footprint "eagle-import:0207_10")
      (libsource (lib "eagle-import") (part "R-US_0207/10"))
    )
    (comp (ref "U$1")
      (value "OUTLINE-DOUBLE")
      (footprint "eagle-import:DOUBLE")
      (libsource (lib "eagle-import") (part "OUTLINE-DOUBLE"))
    )
  )
  (nets
    (net (code "1") (name "-15V") (class "Default")
      (node (ref "A") (pin "B2") (pinfunction "P_B2") (pintype "passive"))
      (node (ref "R1") (pin "1") (pinfunction "1_1") (pintype "passive"))
      (node (ref "R10") (pin "1") (pinfunction "1_1") (pintype "passive"))
      (node (ref "R11") (pin "1") (pinfunction "1_1") (pintype "passive"))
      (node (ref "R12") (pin "1") (pinfunction "1_1") (pintype "passive"))
      (node (ref "R14") (pin "1") (pinfunction "1_1") (pintype "passive"))
      (node (ref "R15") (pin "1") (pinfunction "1_1") (pintype "passive"))
      (node (ref "R17") (pin "1") (pinfunction "1_1") (pintype "passive"))
      (node (ref "R18") (pin "1") (pinfunction "1_1") (pintype "passive"))
      (node (ref "R20") (pin "1") (pinfunction "1_1") (pintype "passive"))
      (node (ref "R21") (pin "1") (pinfunction "1_1") (pintype "passive"))
      (node (ref "R23") (pin "1") (pinfunction "1_1") (pintype "passive"))
      (node (ref "R25") (pin "1") (pinfunction "1_1") (pintype "passive"))
      (node (ref "R26") (pin "1") (pinfunction "1_1") (pintype "passive"))
      (node (ref "R28") (pin "1") (pinfunction "1_1") (pintype "passive"))
      (node (ref "R3") (pin "1") (pinfunction "1_1") (pintype "passive"))
      (node (ref "R30") (pin "1") (pinfunction "1_1") (pintype "passive"))
      (node (ref "R31") (pin "1") (pinfunction "1_1") (pintype "passive"))
      (node (ref "R32") (pin "1") (pinfunction "1_1") (pintype "passive"))
      (node (ref "R34") (pin "1") (pinfunction "1_1") (pintype "passive"))
      (node (ref "R35") (pin "1") (pinfunction "1_1") (pintype "passive"))
      (node (ref "R36") (pin "1") (pinfunction "1_1") (pintype "passive"))
      (node (ref "R38") (pin "1") (pinfunction "1_1") (pintype "passive"))
      (node (ref "R4") (pin "1") (pinfunction "1_1") (pintype "passive"))
      (node (ref "R40") (pin "1") (pinfunction "1_1") (pintype "passive"))
      (node (ref "R41") (pin "1") (pinfunction "1_1") (pintype "passive"))
      (node (ref "R42") (pin "1") (pinfunction "1_1") (pintype "passive"))
      (node (ref "R44") (pin "1") (pinfunction "1_1") (pintype "passive"))
      (node (ref "R46") (pin "1") (pinfunction "1_1") (pintype "passive"))
      (node (ref "R47") (pin "1") (pinfunction "1_1") (pintype "passive"))
      (node (ref "R49") (pin "1") (pinfunction "1_1") (pintype "passive"))
      (node (ref "R50") (pin "1") (pinfunction "1_1") (pintype "passive"))
      (node (ref "R52") (pin "1") (pinfunction "1_1") (pintype "passive"))
      (node (ref "R53") (pin "1") (pinfunction "1_1") (pintype "passive"))
      (node (ref "R54") (pin "1") (pinfunction "1_1") (pintype "passive"))
      (node (ref "R56") (pin "1") (pinfunction "1_1") (pintype "passive"))
      (node (ref "R58") (pin "1") (pinfunction "1_1") (pintype "passive"))
      (node (ref "R59") (pin "1") (pinfunction "1_1") (pintype "passive"))
      (node (ref "R6") (pin "1") (pinfunction "1_1") (pintype "passive"))
      (node (ref "R61") (pin "1") (pinfunction "1_1") (pintype "passive"))
      (node (ref "R62") (pin "1") (pinfunction "1_1") (pintype "passive"))
      (node (ref "R63") (pin "1") (pinfunction "1_1") (pintype "passive"))
      (node (ref "R65") (pin "1") (pinfunction "1_1") (pintype "passive"))
      (node (ref "R7") (pin "1") (pinfunction "1_1") (pintype "passive"))
      (node (ref "R8") (pin "1") (pinfunction "1_1") (pintype "passive"))
    )
    (net (code "2") (name "/-0.7V") (class "Default")
      (node (ref "C7") (pin "2") (pinfunction "2_2") (pintype "passive"))
      (node (ref "D106") (pin "A") (pinfunction "A_A") (pintype "passive"))
      (node (ref "D107") (pin "C") (pinfunction "C_C") (pintype "passive"))
      (node (ref "D16") (pin "C") (pinfunction "C_C") (pintype "passive"))
      (node (ref "D99") (pin "C") (pinfunction "C_C") (pintype "passive"))
    )
    (net (code "3") (name "/-3V") (class "Default")
      (node (ref "C8") (pin "2") (pinfunction "2_2") (pintype "passive"))
      (node (ref "D100") (pin "A") (pinfunction "A_A") (pintype "passive"))
      (node (ref "D104") (pin "C") (pinfunction "C_C") (pintype "passive"))
      (node (ref "D15") (pin "A") (pinfunction "A_A") (pintype "passive"))
      (node (ref "D2") (pin "A") (pinfunction "A_A") (pintype "passive"))
      (node (ref "D28") (pin "A") (pinfunction "A_A") (pintype "passive"))
      (node (ref "D32") (pin "A") (pinfunction "A_A") (pintype "passive"))
      (node (ref "D49") (pin "A") (pinfunction "A_A") (pintype "passive"))
      (node (ref "D5") (pin "A") (pinfunction "A_A") (pintype "passive"))
      (node (ref "D51") (pin "A") (pinfunction "A_A") (pintype "passive"))
      (node (ref "D55") (pin "A") (pinfunction "A_A") (pintype "passive"))
      (node (ref "D61") (pin "A") (pinfunction "A_A") (pintype "passive"))
      (node (ref "D63") (pin "A") (pinfunction "A_A") (pintype "passive"))
      (node (ref "D81") (pin "A") (pinfunction "A_A") (pintype "passive"))
      (node (ref "D85") (pin "A") (pinfunction "A_A") (pintype "passive"))
      (node (ref "R65") (pin "2") (pinfunction "2_2") (pintype "passive"))
    )
    (net (code "4") (name "/ADDR12") (class "Default")
      (node (ref "A") (pin "J2") (pinfunction "P_J2") (pintype "passive"))
      (node (ref "Q4") (pin "3") (pinfunction "C_3") (pintype "passive"))
      (node (ref "R66") (pin "1") (pinfunction "1_1") (pintype "passive"))
      (node (ref "R66") (pin "2") (pinfunction "2_2") (pintype "passive"))
    )
    (net (code "5") (name "/ADDR13") (class "Default")
      (node (ref "A") (pin "K2") (pinfunction "P_K2") (pintype "passive"))
      (node (ref "Q7") (pin "3") (pinfunction "C_3") (pintype "passive"))
      (node (ref "R67") (pin "1") (pinfunction "1_1") (pintype "passive"))
      (node (ref "R67") (pin "2") (pinfunction "2_2") (pintype "passive"))
    )
    (net (code "6") (name "/ADDR14") (class "Default")
      (node (ref "A") (pin "L2") (pinfunction "P_L2") (pintype "passive"))
      (node (ref "Q9") (pin "3") (pinfunction "C_3") (pintype "passive"))
      (node (ref "R68") (pin "1") (pinfunction "1_1") (pintype "passive"))
      (node (ref "R68") (pin "2") (pinfunction "2_2") (pintype "passive"))
    )
    (net (code "7") (name "/ADDR15") (class "Default")
      (node (ref "A") (pin "N2") (pinfunction "P_N2") (pintype "passive"))
      (node (ref "Q15") (pin "3") (pinfunction "C_3") (pintype "passive"))
      (node (ref "R69") (pin "1") (pinfunction "1_1") (pintype "passive"))
      (node (ref "R69") (pin "2") (pinfunction "2_2") (pintype "passive"))
    )
    (net (code "8") (name "/ADDR16") (class "Default")
      (node (ref "A") (pin "S2") (pinfunction "P_S2") (pintype "passive"))
      (node (ref "Q17") (pin "3") (pinfunction "C_3") (pintype "passive"))
      (node (ref "R70") (pin "1") (pinfunction "1_1") (pintype "passive"))
      (node (ref "R70") (pin "2") (pinfunction "2_2") (pintype "passive"))
    )
    (net (code "9") (name "/ADDR17") (class "Default")
      (node (ref "A") (pin "U2") (pinfunction "P_U2") (pintype "passive"))
      (node (ref "Q21") (pin "3") (pinfunction "C_3") (pintype "passive"))
      (node (ref "R71") (pin "1") (pinfunction "1_1") (pintype "passive"))
      (node (ref "R71") (pin "2") (pinfunction "2_2") (pintype "passive"))
    )
    (net (code "10") (name "/CLR_FLG") (class "Default")
      (node (ref "B") (pin "D2") (pinfunction "P_D2") (pintype "passive"))
      (node (ref "D1") (pin "A") (pinfunction "A_A") (pintype "passive"))
      (node (ref "D2") (pin "C") (pinfunction "C_C") (pintype "passive"))
      (node (ref "D4") (pin "A") (pinfunction "A_A") (pintype "passive"))
      (node (ref "Q1") (pin "3") (pinfunction "C_3") (pintype "passive"))
      (node (ref "R1") (pin "2") (pinfunction "2_2") (pintype "passive"))
    )
    (net (code "11") (name "/ENA") (class "Default")
      (node (ref "A") (pin "P2") (pinfunction "P_P2") (pintype "passive"))
      (node (ref "D17") (pin "A") (pinfunction "A_A") (pintype "passive"))
      (node (ref "D27") (pin "A") (pinfunction "A_A") (pintype "passive"))
      (node (ref "D28") (pin "C") (pinfunction "C_C") (pintype "passive"))
      (node (ref "D29") (pin "A") (pinfunction "A_A") (pintype "passive"))
      (node (ref "D37") (pin "A") (pinfunction "A_A") (pintype "passive"))
      (node (ref "D40") (pin "A") (pinfunction "A_A") (pintype "passive"))
      (node (ref "D54") (pin "A") (pinfunction "A_A") (pintype "passive"))
      (node (ref "D78") (pin "A") (pinfunction "A_A") (pintype "passive"))
      (node (ref "D93") (pin "A") (pinfunction "A_A") (pintype "passive"))
      (node (ref "Q6") (pin "3") (pinfunction "C_3") (pintype "passive"))
      (node (ref "R18") (pin "2") (pinfunction "2_2") (pintype "passive"))
    )
    (net (code "12") (name "/ENB") (class "Default")
      (node (ref "A") (pin "E2") (pinfunction "P_E2") (pintype "passive"))
      (node (ref "D56") (pin "A") (pinfunction "A_A") (pintype "passive"))
      (node (ref "D63") (pin "C") (pinfunction "C_C") (pintype "passive"))
      (node (ref "D87") (pin "A") (pinfunction "A_A") (pintype "passive"))
      (node (ref "Q14") (pin "3") (pinfunction "C_3") (pintype "passive"))
      (node (ref "R38") (pin "2") (pinfunction "2_2") (pintype "passive"))
    )
    (net (code "13") (name "/IO_PWR_CLR") (class "Default")
      (node (ref "B") (pin "T2") (pinfunction "P_T2") (pintype "passive"))
      (node (ref "D43") (pin "A") (pinfunction "A_A") (pintype "passive"))
    )
    (net (code "14") (name "/IO_SYNC") (class "Default")
      (node (ref "A") (pin "H2") (pinfunction "P_H2") (pintype "passive"))
      (node (ref "D101") (pin "A") (pinfunction "A_A") (pintype "passive"))
    )
    (net (code "15") (name "/REQ") (class "Default")
      (node (ref "B") (pin "U2") (pinfunction "P_U2") (pintype "passive"))
      (node (ref "D34") (pin "A") (pinfunction "A_A") (pintype "passive"))
      (node (ref "D81") (pin "C") (pinfunction "C_C") (pintype "passive"))
      (node (ref "D82") (pin "A") (pinfunction "A_A") (pintype "passive"))
      (node (ref "Q18") (pin "3") (pinfunction "C_3") (pintype "passive"))
      (node (ref "R50") (pin "2") (pinfunction "2_2") (pintype "passive"))
    )
    (net (code "16") (name "/RQ") (class "Default")
      (node (ref "B") (pin "V2") (pinfunction "P_V2") (pintype "passive"))
      (node (ref "Q8") (pin "3") (pinfunction "C_3") (pintype "passive"))
    )
    (net (code "17") (name "/SELECT") (class "Default")
      (node (ref "A") (pin "D2") (pinfunction "P_D2") (pintype "passive"))
      (node (ref "Q19") (pin "3") (pinfunction "C_3") (pintype "passive"))
    )
    (net (code "18") (name "/~{ENA}") (class "Default")
      (node (ref "A") (pin "V2") (pinfunction "P_V2") (pintype "passive"))
      (node (ref "D32") (pin "C") (pinfunction "C_C") (pintype "passive"))
      (node (ref "D33") (pin "A") (pinfunction "A_A") (pintype "passive"))
      (node (ref "D72") (pin "A") (pinfunction "A_A") (pintype "passive"))
      (node (ref "Q5") (pin "3") (pinfunction "C_3") (pintype "passive"))
      (node (ref "R20") (pin "2") (pinfunction "2_2") (pintype "passive"))
      (node (ref "R72") (pin "1") (pinfunction "1_1") (pintype "passive"))
      (node (ref "R72") (pin "2") (pinfunction "2_2") (pintype "passive"))
    )
    (net (code "19") (name "/~{ENB}") (class "Default")
      (node (ref "A") (pin "F2") (pinfunction "P_F2") (pintype "passive"))
      (node (ref "D55") (pin "C") (pinfunction "C_C") (pintype "passive"))
      (node (ref "D64") (pin "A") (pinfunction "A_A") (pintype "passive"))
      (node (ref "Q12") (pin "3") (pinfunction "C_3") (pintype "passive"))
      (node (ref "R41") (pin "2") (pinfunction "2_2") (pintype "passive"))
    )
    (net (code "20") (name "/~{REQ}") (class "Default")
      (node (ref "B") (pin "J2") (pinfunction "P_J2") (pintype "passive"))
      (node (ref "D10") (pin "A") (pinfunction "A_A") (pintype "passive"))
      (node (ref "D70") (pin "A") (pinfunction "A_A") (pintype "passive"))
      (node (ref "D85") (pin "C") (pinfunction "C_C") (pintype "passive"))
      (node (ref "D86") (pin "A") (pinfunction "A_A") (pintype "passive"))
      (node (ref "Q16") (pin "3") (pinfunction "C_3") (pintype "passive"))
      (node (ref "R53") (pin "2") (pinfunction "2_2") (pintype "passive"))
    )
    (net (code "21") (name "GND") (class "Default")
      (node (ref "A") (pin "C2") (pinfunction "P_C2") (pintype "passive"))
      (node (ref "B") (pin "C2") (pinfunction "P_C2") (pintype "passive"))
      (node (ref "C7") (pin "1") (pinfunction "1_1") (pintype "passive"))
      (node (ref "C8") (pin "1") (pinfunction "1_1") (pintype "passive"))
      (node (ref "D107") (pin "A") (pinfunction "A_A") (pintype "passive"))
      (node (ref "D3") (pin "C") (pinfunction "C_C") (pintype "passive"))
      (node (ref "Q1") (pin "1") (pinfunction "E_1") (pintype "passive"))
      (node (ref "Q10") (pin "1") (pinfunction "E_1") (pintype "passive"))
      (node (ref "Q11") (pin "1") (pinfunction "E_1") (pintype "passive"))
      (node (ref "Q12") (pin "1") (pinfunction "E_1") (pintype "passive"))
      (node (ref "Q13") (pin "1") (pinfunction "E_1") (pintype "passive"))
      (node (ref "Q14") (pin "1") (pinfunction "E_1") (pintype "passive"))
      (node (ref "Q15") (pin "1") (pinfunction "E_1") (pintype "passive"))
      (node (ref "Q16") (pin "1") (pinfunction "E_1") (pintype "passive"))
      (node (ref "Q17") (pin "1") (pinfunction "E_1") (pintype "passive"))
      (node (ref "Q18") (pin "1") (pinfunction "E_1") (pintype "passive"))
      (node (ref "Q19") (pin "1") (pinfunction "E_1") (pintype "passive"))
      (node (ref "Q2") (pin "1") (pinfunction "E_1") (pintype "passive"))
      (node (ref "Q20") (pin "1") (pinfunction "E_1") (pintype "passive"))
      (node (ref "Q21") (pin "1") (pinfunction "E_1") (pintype "passive"))
      (node (ref "Q3") (pin "1") (pinfunction "E_1") (pintype "passive"))
      (node (ref "Q4") (pin "1") (pinfunction "E_1") (pintype "passive"))
      (node (ref "Q5") (pin "1") (pinfunction "E_1") (pintype "passive"))
      (node (ref "Q6") (pin "1") (pinfunction "E_1") (pintype "passive"))
      (node (ref "Q7") (pin "1") (pinfunction "E_1") (pintype "passive"))
      (node (ref "Q8") (pin "1") (pinfunction "E_1") (pintype "passive"))
      (node (ref "Q9") (pin "1") (pinfunction "E_1") (pintype "passive"))
    )
    (net (code "22") (name "Net-(BE-P)") (class "Default")
      (node (ref "B") (pin "E2") (pinfunction "P_E2") (pintype "passive"))
      (node (ref "D13") (pin "A") (pinfunction "A_A") (pintype "passive"))
      (node (ref "D16") (pin "A") (pinfunction "A_A") (pintype "passive"))
      (node (ref "D20") (pin "A") (pinfunction "A_A") (pintype "passive"))
    )
    (net (code "23") (name "Net-(BF-P)") (class "Default")
      (node (ref "B") (pin "F2") (pinfunction "P_F2") (pintype "passive"))
      (node (ref "D75") (pin "A") (pinfunction "A_A") (pintype "passive"))
    )
    (net (code "24") (name "Net-(BG-P)") (class "Default")
      (node (ref "B") (pin "H2") (pinfunction "P_H2") (pintype "passive"))
      (node (ref "D69") (pin "A") (pinfunction "A_A") (pintype "passive"))
      (node (ref "D73") (pin "A") (pinfunction "A_A") (pintype "passive"))
    )
    (net (code "25") (name "Net-(BK-P)") (class "Default")
      (node (ref "B") (pin "M2") (pinfunction "P_M2") (pintype "passive"))
      (node (ref "D51") (pin "C") (pinfunction "C_C") (pintype "passive"))
      (node (ref "Q11") (pin "3") (pinfunction "C_3") (pintype "passive"))
      (node (ref "R34") (pin "2") (pinfunction "2_2") (pintype "passive"))
    )
    (net (code "26") (name "Net-(BO-P)") (class "Default")
      (node (ref "B") (pin "S2") (pinfunction "P_S2") (pintype "passive"))
      (node (ref "D96") (pin "A") (pinfunction "A_A") (pintype "passive"))
      (node (ref "D99") (pin "A") (pinfunction "A_A") (pintype "passive"))
    )
    (net (code "27") (name "Net-(C2-Pad1)") (class "Default")
      (node (ref "C2") (pin "1") (pinfunction "1_1") (pintype "passive"))
      (node (ref "D10") (pin "C") (pinfunction "C_C") (pintype "passive"))
      (node (ref "D8") (pin "A") (pinfunction "A_A") (pintype "passive"))
      (node (ref "D9") (pin "C") (pinfunction "C_C") (pintype "passive"))
      (node (ref "R6") (pin "2") (pinfunction "2_2") (pintype "passive"))
    )
    (net (code "28") (name "Net-(C2-Pad2)") (class "Default")
      (node (ref "C2") (pin "2") (pinfunction "2_2") (pintype "passive"))
      (node (ref "D14") (pin "C") (pinfunction "C_C") (pintype "passive"))
      (node (ref "D9") (pin "A") (pinfunction "A_A") (pintype "passive"))
      (node (ref "R7") (pin "2") (pinfunction "2_2") (pintype "passive"))
    )
    (net (code "29") (name "Net-(C3-Pad1)") (class "Default")
      (node (ref "C3") (pin "1") (pinfunction "1_1") (pintype "passive"))
      (node (ref "D21") (pin "C") (pinfunction "C_C") (pintype "passive"))
      (node (ref "D22") (pin "A") (pinfunction "A_A") (pintype "passive"))
      (node (ref "R12") (pin "2") (pinfunction "2_2") (pintype "passive"))
    )
    (net (code "30") (name "Net-(C3-Pad2)") (class "Default")
      (node (ref "C3") (pin "2") (pinfunction "2_2") (pintype "passive"))
      (node (ref "D20") (pin "C") (pinfunction "C_C") (pintype "passive"))
      (node (ref "D22") (pin "C") (pinfunction "C_C") (pintype "passive"))
      (node (ref "D23") (pin "A") (pinfunction "A_A") (pintype "passive"))
      (node (ref "R14") (pin "2") (pinfunction "2_2") (pintype "passive"))
    )
    (net (code "31") (name "Net-(C4-Pad1)") (class "Default")
      (node (ref "C4") (pin "1") (pinfunction "1_1") (pintype "passive"))
      (node (ref "D44") (pin "C") (pinfunction "C_C") (pintype "passive"))
      (node (ref "D47") (pin "A") (pinfunction "A_A") (pintype "passive"))
      (node (ref "R26") (pin "2") (pinfunction "2_2") (pintype "passive"))
    )
    (net (code "32") (name "Net-(C4-Pad2)") (class "Default")
      (node (ref "C4") (pin "2") (pinfunction "2_2") (pintype "passive"))
      (node (ref "D37") (pin "C") (pinfunction "C_C") (pintype "passive"))
      (node (ref "D47") (pin "C") (pinfunction "C_C") (pintype "passive"))
      (node (ref "D48") (pin "A") (pinfunction "A_A") (pintype "passive"))
      (node (ref "R30") (pin "2") (pinfunction "2_2") (pintype "passive"))
    )
    (net (code "33") (name "Net-(C5-Pad1)") (class "Default")
      (node (ref "C5") (pin "1") (pinfunction "1_1") (pintype "passive"))
      (node (ref "D71") (pin "A") (pinfunction "A_A") (pintype "passive"))
      (node (ref "D72") (pin "C") (pinfunction "C_C") (pintype "passive"))
      (node (ref "D83") (pin "C") (pinfunction "C_C") (pintype "passive"))
      (node (ref "R46") (pin "2") (pinfunction "2_2") (pintype "passive"))
    )
    (net (code "34") (name "Net-(C5-Pad2)") (class "Default")
      (node (ref "C5") (pin "2") (pinfunction "2_2") (pintype "passive"))
      (node (ref "D83") (pin "A") (pinfunction "A_A") (pintype "passive"))
      (node (ref "D84") (pin "C") (pinfunction "C_C") (pintype "passive"))
      (node (ref "R52") (pin "2") (pinfunction "2_2") (pintype "passive"))
    )
    (net (code "35") (name "Net-(C6-Pad1)") (class "Default")
      (node (ref "C6") (pin "1") (pinfunction "1_1") (pintype "passive"))
      (node (ref "D92") (pin "A") (pinfunction "A_A") (pintype "passive"))
      (node (ref "D96") (pin "C") (pinfunction "C_C") (pintype "passive"))
      (node (ref "D97") (pin "C") (pinfunction "C_C") (pintype "passive"))
      (node (ref "R59") (pin "2") (pinfunction "2_2") (pintype "passive"))
    )
    (net (code "36") (name "Net-(C6-Pad2)") (class "Default")
      (node (ref "C6") (pin "2") (pinfunction "2_2") (pintype "passive"))
      (node (ref "D97") (pin "A") (pinfunction "A_A") (pintype "passive"))
      (node (ref "D98") (pin "C") (pinfunction "C_C") (pintype "passive"))
      (node (ref "R61") (pin "2") (pinfunction "2_2") (pintype "passive"))
    )
    (net (code "37") (name "Net-(D1-PadC)") (class "Default")
      (node (ref "D1") (pin "C") (pinfunction "C_C") (pintype "passive"))
      (node (ref "D33") (pin "C") (pinfunction "C_C") (pintype "passive"))
      (node (ref "D35") (pin "C") (pinfunction "C_C") (pintype "passive"))
      (node (ref "R21") (pin "2") (pinfunction "2_2") (pintype "passive"))
    )
    (net (code "38") (name "Net-(D4-PadC)") (class "Default")
      (node (ref "D4") (pin "C") (pinfunction "C_C") (pintype "passive"))
      (node (ref "D6") (pin "C") (pinfunction "C_C") (pintype "passive"))
      (node (ref "R4") (pin "2") (pinfunction "2_2") (pintype "passive"))
    )
    (net (code "39") (name "Net-(D6-PadA)") (class "Default")
      (node (ref "D6") (pin "A") (pinfunction "A_A") (pintype "passive"))
      (node (ref "D7") (pin "C") (pinfunction "C_C") (pintype "passive"))
    )
    (net (code "40") (name "Net-(D11-PadA)") (class "Default")
      (node (ref "D11") (pin "A") (pinfunction "A_A") (pintype "passive"))
      (node (ref "D12") (pin "C") (pinfunction "C_C") (pintype "passive"))
    )
    (net (code "41") (name "Net-(D11-PadC)") (class "Default")
      (node (ref "D11") (pin "C") (pinfunction "C_C") (pintype "passive"))
      (node (ref "D13") (pin "C") (pinfunction "C_C") (pintype "passive"))
      (node (ref "R8") (pin "2") (pinfunction "2_2") (pintype "passive"))
    )
    (net (code "42") (name "Net-(D17-PadC)") (class "Default")
      (node (ref "D17") (pin "C") (pinfunction "C_C") (pintype "passive"))
      (node (ref "D18") (pin "C") (pinfunction "C_C") (pintype "passive"))
      (node (ref "R11") (pin "2") (pinfunction "2_2") (pintype "passive"))
    )
    (net (code "43") (name "Net-(D18-PadA)") (class "Default")
      (node (ref "D18") (pin "A") (pinfunction "A_A") (pintype "passive"))
      (node (ref "D19") (pin "C") (pinfunction "C_C") (pintype "passive"))
    )
    (net (code "44") (name "Net-(D24-PadC)") (class "Default")
      (node (ref "D24") (pin "C") (pinfunction "C_C") (pintype "passive"))
      (node (ref "D25") (pin "C") (pinfunction "C_C") (pintype "passive"))
      (node (ref "D29") (pin "C") (pinfunction "C_C") (pintype "passive"))
      (node (ref "R15") (pin "2") (pinfunction "2_2") (pintype "passive"))
    )
    (net (code "45") (name "Net-(D25-PadA)") (class "Default")
      (node (ref "D25") (pin "A") (pinfunction "A_A") (pintype "passive"))
      (node (ref "D26") (pin "C") (pinfunction "C_C") (pintype "passive"))
    )
    (net (code "46") (name "Net-(D27-PadC)") (class "Default")
      (node (ref "D27") (pin "C") (pinfunction "C_C") (pintype "passive"))
      (node (ref "D30") (pin "C") (pinfunction "C_C") (pintype "passive"))
      (node (ref "R17") (pin "2") (pinfunction "2_2") (pintype "passive"))
    )
    (net (code "47") (name "Net-(D30-PadA)") (class "Default")
      (node (ref "D30") (pin "A") (pinfunction "A_A") (pintype "passive"))
      (node (ref "D31") (pin "C") (pinfunction "C_C") (pintype "passive"))
    )
    (net (code "48") (name "Net-(D34-PadC)") (class "Default")
      (node (ref "D34") (pin "C") (pinfunction "C_C") (pintype "passive"))
      (node (ref "D38") (pin "C") (pinfunction "C_C") (pintype "passive"))
      (node (ref "R23") (pin "2") (pinfunction "2_2") (pintype "passive"))
    )
    (net (code "49") (name "Net-(D35-PadA)") (class "Default")
      (node (ref "D35") (pin "A") (pinfunction "A_A") (pintype "passive"))
      (node (ref "D36") (pin "C") (pinfunction "C_C") (pintype "passive"))
    )
    (net (code "50") (name "Net-(D38-PadA)") (class "Default")
      (node (ref "D38") (pin "A") (pinfunction "A_A") (pintype "passive"))
      (node (ref "D39") (pin "C") (pinfunction "C_C") (pintype "passive"))
    )
    (net (code "51") (name "Net-(D40-PadC)") (class "Default")
      (node (ref "D40") (pin "C") (pinfunction "C_C") (pintype "passive"))
      (node (ref "D41") (pin "C") (pinfunction "C_C") (pintype "passive"))
      (node (ref "R25") (pin "2") (pinfunction "2_2") (pintype "passive"))
    )
    (net (code "52") (name "Net-(D41-PadA)") (class "Default")
      (node (ref "D41") (pin "A") (pinfunction "A_A") (pintype "passive"))
      (node (ref "D42") (pin "C") (pinfunction "C_C") (pintype "passive"))
    )
    (net (code "53") (name "Net-(D43-PadC)") (class "Default")
      (node (ref "D43") (pin "C") (pinfunction "C_C") (pintype "passive"))
      (node (ref "D45") (pin "C") (pinfunction "C_C") (pintype "passive"))
      (node (ref "R28") (pin "2") (pinfunction "2_2") (pintype "passive"))
    )
    (net (code "54") (name "Net-(D45-PadA)") (class "Default")
      (node (ref "D45") (pin "A") (pinfunction "A_A") (pintype "passive"))
      (node (ref "D46") (pin "C") (pinfunction "C_C") (pintype "passive"))
    )
    (net (code "55") (name "Net-(D50-PadC)") (class "Default")
      (node (ref "D50") (pin "C") (pinfunction "C_C") (pintype "passive"))
      (node (ref "D52") (pin "C") (pinfunction "C_C") (pintype "passive"))
      (node (ref "D56") (pin "C") (pinfunction "C_C") (pintype "passive"))
      (node (ref "R32") (pin "2") (pinfunction "2_2") (pintype "passive"))
    )
    (net (code "56") (name "Net-(D52-PadA)") (class "Default")
      (node (ref "D52") (pin "A") (pinfunction "A_A") (pintype "passive"))
      (node (ref "D53") (pin "C") (pinfunction "C_C") (pintype "passive"))
    )
    (net (code "57") (name "Net-(D54-PadC)") (class "Default")
      (node (ref "D54") (pin "C") (pinfunction "C_C") (pintype "passive"))
      (node (ref "D57") (pin "C") (pinfunction "C_C") (pintype "passive"))
      (node (ref "R35") (pin "2") (pinfunction "2_2") (pintype "passive"))
    )
    (net (code "58") (name "Net-(D57-PadA)") (class "Default")
      (node (ref "D57") (pin "A") (pinfunction "A_A") (pintype "passive"))
      (node (ref "D60") (pin "C") (pinfunction "C_C") (pintype "passive"))
    )
    (net (code "59") (name "Net-(D58-PadA)") (class "Default")
      (node (ref "D58") (pin "A") (pinfunction "A_A") (pintype "passive"))
      (node (ref "D59") (pin "C") (pinfunction "C_C") (pintype "passive"))
    )
    (net (code "60") (name "Net-(D58-PadC)") (class "Default")
      (node (ref "D58") (pin "C") (pinfunction "C_C") (pintype "passive"))
      (node (ref "D62") (pin "C") (pinfunction "C_C") (pintype "passive"))
      (node (ref "R36") (pin "2") (pinfunction "2_2") (pintype "passive"))
    )
    (net (code "61") (name "Net-(D64-PadC)") (class "Default")
      (node (ref "D64") (pin "C") (pinfunction "C_C") (pintype "passive"))
      (node (ref "D67") (pin "C") (pinfunction "C_C") (pintype "passive"))
      (node (ref "R44") (pin "2") (pinfunction "2_2") (pintype "passive"))
    )
    (net (code "62") (name "Net-(D65-PadA)") (class "Default")
      (node (ref "D65") (pin "A") (pinfunction "A_A") (pintype "passive"))
      (node (ref "D66") (pin "C") (pinfunction "C_C") (pintype "passive"))
    )
    (net (code "63") (name "Net-(D65-PadC)") (class "Default")
      (node (ref "D65") (pin "C") (pinfunction "C_C") (pintype "passive"))
      (node (ref "D69") (pin "C") (pinfunction "C_C") (pintype "passive"))
      (node (ref "D70") (pin "C") (pinfunction "C_C") (pintype "passive"))
      (node (ref "R42") (pin "2") (pinfunction "2_2") (pintype "passive"))
    )
    (net (code "64") (name "Net-(D67-PadA)") (class "Default")
      (node (ref "D67") (pin "A") (pinfunction "A_A") (pintype "passive"))
      (node (ref "D68") (pin "C") (pinfunction "C_C") (pintype "passive"))
    )
    (net (code "65") (name "Net-(D73-PadC)") (class "Default")
      (node (ref "D73") (pin "C") (pinfunction "C_C") (pintype "passive"))
      (node (ref "D74") (pin "C") (pinfunction "C_C") (pintype "passive"))
      (node (ref "D75") (pin "C") (pinfunction "C_C") (pintype "passive"))
      (node (ref "D76") (pin "C") (pinfunction "C_C") (pintype "passive"))
      (node (ref "D82") (pin "C") (pinfunction "C_C") (pintype "passive"))
      (node (ref "R47") (pin "2") (pinfunction "2_2") (pintype "passive"))
    )
    (net (code "66") (name "Net-(D76-PadA)") (class "Default")
      (node (ref "D76") (pin "A") (pinfunction "A_A") (pintype "passive"))
      (node (ref "D77") (pin "C") (pinfunction "C_C") (pintype "passive"))
    )
    (net (code "67") (name "Net-(D78-PadC)") (class "Default")
      (node (ref "D78") (pin "C") (pinfunction "C_C") (pintype "passive"))
      (node (ref "D79") (pin "C") (pinfunction "C_C") (pintype "passive"))
      (node (ref "R49") (pin "2") (pinfunction "2_2") (pintype "passive"))
    )
    (net (code "68") (name "Net-(D79-PadA)") (class "Default")
      (node (ref "D79") (pin "A") (pinfunction "A_A") (pintype "passive"))
      (node (ref "D80") (pin "C") (pinfunction "C_C") (pintype "passive"))
    )
    (net (code "69") (name "Net-(D86-PadC)") (class "Default")
      (node (ref "D86") (pin "C") (pinfunction "C_C") (pintype "passive"))
      (node (ref "D90") (pin "C") (pinfunction "C_C") (pintype "passive"))
      (node (ref "R56") (pin "2") (pinfunction "2_2") (pintype "passive"))
    )
    (net (code "70") (name "Net-(D87-PadC)") (class "Default")
      (node (ref "D87") (pin "C") (pinfunction "C_C") (pintype "passive"))
      (node (ref "D88") (pin "C") (pinfunction "C_C") (pintype "passive"))
      (node (ref "R54") (pin "2") (pinfunction "2_2") (pintype "passive"))
    )
    (net (code "71") (name "Net-(D88-PadA)") (class "Default")
      (node (ref "D88") (pin "A") (pinfunction "A_A") (pintype "passive"))
      (node (ref "D89") (pin "C") (pinfunction "C_C") (pintype "passive"))
    )
    (net (code "72") (name "Net-(D90-PadA)") (class "Default")
      (node (ref "D90") (pin "A") (pinfunction "A_A") (pintype "passive"))
      (node (ref "D91") (pin "C") (pinfunction "C_C") (pintype "passive"))
    )
    (net (code "73") (name "Net-(D93-PadC)") (class "Default")
      (node (ref "D93") (pin "C") (pinfunction "C_C") (pintype "passive"))
      (node (ref "D94") (pin "C") (pinfunction "C_C") (pintype "passive"))
      (node (ref "R58") (pin "2") (pinfunction "2_2") (pintype "passive"))
    )
    (net (code "74") (name "Net-(D94-PadA)") (class "Default")
      (node (ref "D94") (pin "A") (pinfunction "A_A") (pintype "passive"))
      (node (ref "D95") (pin "C") (pinfunction "C_C") (pintype "passive"))
    )
    (net (code "75") (name "Net-(D101-PadC)") (class "Default")
      (node (ref "D101") (pin "C") (pinfunction "C_C") (pintype "passive"))
      (node (ref "D102") (pin "C") (pinfunction "C_C") (pintype "passive"))
      (node (ref "R63") (pin "2") (pinfunction "2_2") (pintype "passive"))
    )
    (net (code "76") (name "Net-(D102-PadA)") (class "Default")
      (node (ref "D102") (pin "A") (pinfunction "A_A") (pintype "passive"))
      (node (ref "D103") (pin "C") (pinfunction "C_C") (pintype "passive"))
    )
    (net (code "77") (name "Net-(D104-PadA)") (class "Default")
      (node (ref "D104") (pin "A") (pinfunction "A_A") (pintype "passive"))
      (node (ref "D105") (pin "C") (pinfunction "C_C") (pintype "passive"))
    )
    (net (code "78") (name "Net-(D105-PadA)") (class "Default")
      (node (ref "D105") (pin "A") (pinfunction "A_A") (pintype "passive"))
      (node (ref "D106") (pin "C") (pinfunction "C_C") (pintype "passive"))
    )
    (net (code "79") (name "Net-(Q1-B)") (class "Default")
      (node (ref "C1") (pin "1") (pinfunction "1_1") (pintype "passive"))
      (node (ref "D3") (pin "A") (pinfunction "A_A") (pintype "passive"))
      (node (ref "Q1") (pin "2") (pinfunction "B_2") (pintype "passive"))
      (node (ref "R2") (pin "1") (pinfunction "1_1") (pintype "passive"))
    )
    (net (code "80") (name "Net-(Q2-B)") (class "Default")
      (node (ref "D7") (pin "A") (pinfunction "A_A") (pintype "passive"))
      (node (ref "D8") (pin "C") (pinfunction "C_C") (pintype "passive"))
      (node (ref "Q2") (pin "2") (pinfunction "B_2") (pintype "passive"))
      (node (ref "R5") (pin "1") (pinfunction "1_1") (pintype "passive"))
    )
    (net (code "81") (name "Net-(Q2-C)") (class "Default")
      (node (ref "C1") (pin "2") (pinfunction "2_2") (pintype "passive"))
      (node (ref "D5") (pin "C") (pinfunction "C_C") (pintype "passive"))
      (node (ref "Q2") (pin "3") (pinfunction "C_3") (pintype "passive"))
      (node (ref "R3") (pin "2") (pinfunction "2_2") (pintype "passive"))
    )
    (net (code "82") (name "Net-(Q3-B)") (class "Default")
      (node (ref "D12") (pin "A") (pinfunction "A_A") (pintype "passive"))
      (node (ref "Q3") (pin "2") (pinfunction "B_2") (pintype "passive"))
      (node (ref "R9") (pin "1") (pinfunction "1_1") (pintype "passive"))
    )
    (net (code "83") (name "Net-(Q3-C)") (class "Default")
      (node (ref "D14") (pin "A") (pinfunction "A_A") (pintype "passive"))
      (node (ref "D15") (pin "C") (pinfunction "C_C") (pintype "passive"))
      (node (ref "Q3") (pin "3") (pinfunction "C_3") (pintype "passive"))
      (node (ref "R10") (pin "2") (pinfunction "2_2") (pintype "passive"))
    )
    (net (code "84") (name "Net-(Q4-B)") (class "Default")
      (node (ref "D19") (pin "A") (pinfunction "A_A") (pintype "passive"))
      (node (ref "Q4") (pin "2") (pinfunction "B_2") (pintype "passive"))
      (node (ref "R13") (pin "1") (pinfunction "1_1") (pintype "passive"))
    )
    (net (code "85") (name "Net-(Q5-B)") (class "Default")
      (node (ref "D23") (pin "C") (pinfunction "C_C") (pintype "passive"))
      (node (ref "D26") (pin "A") (pinfunction "A_A") (pintype "passive"))
      (node (ref "Q5") (pin "2") (pinfunction "B_2") (pintype "passive"))
      (node (ref "R16") (pin "1") (pinfunction "1_1") (pintype "passive"))
    )
    (net (code "86") (name "Net-(Q6-B)") (class "Default")
      (node (ref "D36") (pin "A") (pinfunction "A_A") (pintype "passive"))
      (node (ref "Q6") (pin "2") (pinfunction "B_2") (pintype "passive"))
      (node (ref "R22") (pin "1") (pinfunction "1_1") (pintype "passive"))
    )
    (net (code "87") (name "Net-(Q7-B)") (class "Default")
      (node (ref "D31") (pin "A") (pinfunction "A_A") (pintype "passive"))
      (node (ref "Q7") (pin "2") (pinfunction "B_2") (pintype "passive"))
      (node (ref "R19") (pin "1") (pinfunction "1_1") (pintype "passive"))
    )
    (net (code "88") (name "Net-(Q8-B)") (class "Default")
      (node (ref "D39") (pin "A") (pinfunction "A_A") (pintype "passive"))
      (node (ref "Q8") (pin "2") (pinfunction "B_2") (pintype "passive"))
      (node (ref "R24") (pin "1") (pinfunction "1_1") (pintype "passive"))
    )
    (net (code "89") (name "Net-(Q9-B)") (class "Default")
      (node (ref "D42") (pin "A") (pinfunction "A_A") (pintype "passive"))
      (node (ref "Q9") (pin "2") (pinfunction "B_2") (pintype "passive"))
      (node (ref "R27") (pin "1") (pinfunction "1_1") (pintype "passive"))
    )
    (net (code "90") (name "Net-(Q10-B)") (class "Default")
      (node (ref "D46") (pin "A") (pinfunction "A_A") (pintype "passive"))
      (node (ref "Q10") (pin "2") (pinfunction "B_2") (pintype "passive"))
      (node (ref "R29") (pin "1") (pinfunction "1_1") (pintype "passive"))
    )
    (net (code "91") (name "Net-(Q10-C)") (class "Default")
      (node (ref "D24") (pin "A") (pinfunction "A_A") (pintype "passive"))
      (node (ref "D49") (pin "C") (pinfunction "C_C") (pintype "passive"))
      (node (ref "D50") (pin "A") (pinfunction "A_A") (pintype "passive"))
      (node (ref "D74") (pin "A") (pinfunction "A_A") (pintype "passive"))
      (node (ref "Q10") (pin "3") (pinfunction "C_3") (pintype "passive"))
      (node (ref "R31") (pin "2") (pinfunction "2_2") (pintype "passive"))
    )
    (net (code "92") (name "Net-(Q11-B)") (class "Default")
      (node (ref "D59") (pin "A") (pinfunction "A_A") (pintype "passive"))
      (node (ref "Q11") (pin "2") (pinfunction "B_2") (pintype "passive"))
      (node (ref "R37") (pin "1") (pinfunction "1_1") (pintype "passive"))
    )
    (net (code "93") (name "Net-(Q12-B)") (class "Default")
      (node (ref "D48") (pin "C") (pinfunction "C_C") (pintype "passive"))
      (node (ref "D53") (pin "A") (pinfunction "A_A") (pintype "passive"))
      (node (ref "Q12") (pin "2") (pinfunction "B_2") (pintype "passive"))
      (node (ref "R33") (pin "1") (pinfunction "1_1") (pintype "passive"))
    )
    (net (code "94") (name "Net-(Q13-B)") (class "Default")
      (node (ref "D66") (pin "A") (pinfunction "A_A") (pintype "passive"))
      (node (ref "Q13") (pin "2") (pinfunction "B_2") (pintype "passive"))
      (node (ref "R43") (pin "1") (pinfunction "1_1") (pintype "passive"))
    )
    (net (code "95") (name "Net-(Q13-C)") (class "Default")
      (node (ref "D61") (pin "C") (pinfunction "C_C") (pintype "passive"))
      (node (ref "D62") (pin "A") (pinfunction "A_A") (pintype "passive"))
      (node (ref "Q13") (pin "3") (pinfunction "C_3") (pintype "passive"))
      (node (ref "R40") (pin "2") (pinfunction "2_2") (pintype "passive"))
    )
    (net (code "96") (name "Net-(Q14-B)") (class "Default")
      (node (ref "D68") (pin "A") (pinfunction "A_A") (pintype "passive"))
      (node (ref "D71") (pin "C") (pinfunction "C_C") (pintype "passive"))
      (node (ref "Q14") (pin "2") (pinfunction "B_2") (pintype "passive"))
      (node (ref "R45") (pin "1") (pinfunction "1_1") (pintype "passive"))
    )
    (net (code "97") (name "Net-(Q15-B)") (class "Default")
      (node (ref "D60") (pin "A") (pinfunction "A_A") (pintype "passive"))
      (node (ref "Q15") (pin "2") (pinfunction "B_2") (pintype "passive"))
      (node (ref "R39") (pin "1") (pinfunction "1_1") (pintype "passive"))
    )
    (net (code "98") (name "Net-(Q16-B)") (class "Default")
      (node (ref "D77") (pin "A") (pinfunction "A_A") (pintype "passive"))
      (node (ref "Q16") (pin "2") (pinfunction "B_2") (pintype "passive"))
      (node (ref "R48") (pin "1") (pinfunction "1_1") (pintype "passive"))
    )
    (net (code "99") (name "Net-(Q17-B)") (class "Default")
      (node (ref "D80") (pin "A") (pinfunction "A_A") (pintype "passive"))
      (node (ref "Q17") (pin "2") (pinfunction "B_2") (pintype "passive"))
      (node (ref "R51") (pin "1") (pinfunction "1_1") (pintype "passive"))
    )
    (net (code "100") (name "Net-(Q18-B)") (class "Default")
      (node (ref "D91") (pin "A") (pinfunction "A_A") (pintype "passive"))
      (node (ref "D92") (pin "C") (pinfunction "C_C") (pintype "passive"))
      (node (ref "Q18") (pin "2") (pinfunction "B_2") (pintype "passive"))
      (node (ref "R57") (pin "1") (pinfunction "1_1") (pintype "passive"))
    )
    (net (code "101") (name "Net-(Q19-B)") (class "Default")
      (node (ref "D89") (pin "A") (pinfunction "A_A") (pintype "passive"))
      (node (ref "Q19") (pin "2") (pinfunction "B_2") (pintype "passive"))
      (node (ref "R55") (pin "1") (pinfunction "1_1") (pintype "passive"))
    )
    (net (code "102") (name "Net-(Q20-B)") (class "Default")
      (node (ref "D103") (pin "A") (pinfunction "A_A") (pintype "passive"))
      (node (ref "Q20") (pin "2") (pinfunction "B_2") (pintype "passive"))
      (node (ref "R64") (pin "1") (pinfunction "1_1") (pintype "passive"))
    )
    (net (code "103") (name "Net-(Q20-C)") (class "Default")
      (node (ref "D100") (pin "C") (pinfunction "C_C") (pintype "passive"))
      (node (ref "D21") (pin "A") (pinfunction "A_A") (pintype "passive"))
      (node (ref "D44") (pin "A") (pinfunction "A_A") (pintype "passive"))
      (node (ref "D84") (pin "A") (pinfunction "A_A") (pintype "passive"))
      (node (ref "D98") (pin "A") (pinfunction "A_A") (pintype "passive"))
      (node (ref "Q20") (pin "3") (pinfunction "C_3") (pintype "passive"))
      (node (ref "R62") (pin "2") (pinfunction "2_2") (pintype "passive"))
    )
    (net (code "104") (name "Net-(Q21-B)") (class "Default")
      (node (ref "D95") (pin "A") (pinfunction "A_A") (pintype "passive"))
      (node (ref "Q21") (pin "2") (pinfunction "B_2") (pintype "passive"))
      (node (ref "R60") (pin "1") (pinfunction "1_1") (pintype "passive"))
    )
    (net (code "105") (name "VCC") (class "Default")
      (node (ref "A") (pin "A2") (pinfunction "P_A2") (pintype "passive"))
      (node (ref "R13") (pin "2") (pinfunction "2_2") (pintype "passive"))
      (node (ref "R16") (pin "2") (pinfunction "2_2") (pintype "passive"))
      (node (ref "R19") (pin "2") (pinfunction "2_2") (pintype "passive"))
      (node (ref "R2") (pin "2") (pinfunction "2_2") (pintype "passive"))
      (node (ref "R22") (pin "2") (pinfunction "2_2") (pintype "passive"))
      (node (ref "R24") (pin "2") (pinfunction "2_2") (pintype "passive"))
      (node (ref "R27") (pin "2") (pinfunction "2_2") (pintype "passive"))
      (node (ref "R29") (pin "2") (pinfunction "2_2") (pintype "passive"))
      (node (ref "R33") (pin "2") (pinfunction "2_2") (pintype "passive"))
      (node (ref "R37") (pin "2") (pinfunction "2_2") (pintype "passive"))
      (node (ref "R39") (pin "2") (pinfunction "2_2") (pintype "passive"))
      (node (ref "R43") (pin "2") (pinfunction "2_2") (pintype "passive"))
      (node (ref "R45") (pin "2") (pinfunction "2_2") (pintype "passive"))
      (node (ref "R48") (pin "2") (pinfunction "2_2") (pintype "passive"))
      (node (ref "R5") (pin "2") (pinfunction "2_2") (pintype "passive"))
      (node (ref "R51") (pin "2") (pinfunction "2_2") (pintype "passive"))
      (node (ref "R55") (pin "2") (pinfunction "2_2") (pintype "passive"))
      (node (ref "R57") (pin "2") (pinfunction "2_2") (pintype "passive"))
      (node (ref "R60") (pin "2") (pinfunction "2_2") (pintype "passive"))
      (node (ref "R64") (pin "2") (pinfunction "2_2") (pintype "passive"))
      (node (ref "R9") (pin "2") (pinfunction "2_2") (pintype "passive"))
    )
  )
)
